# ESP8266-ESP201.net
KiCad netlist of a schematic drawn in EAGLE
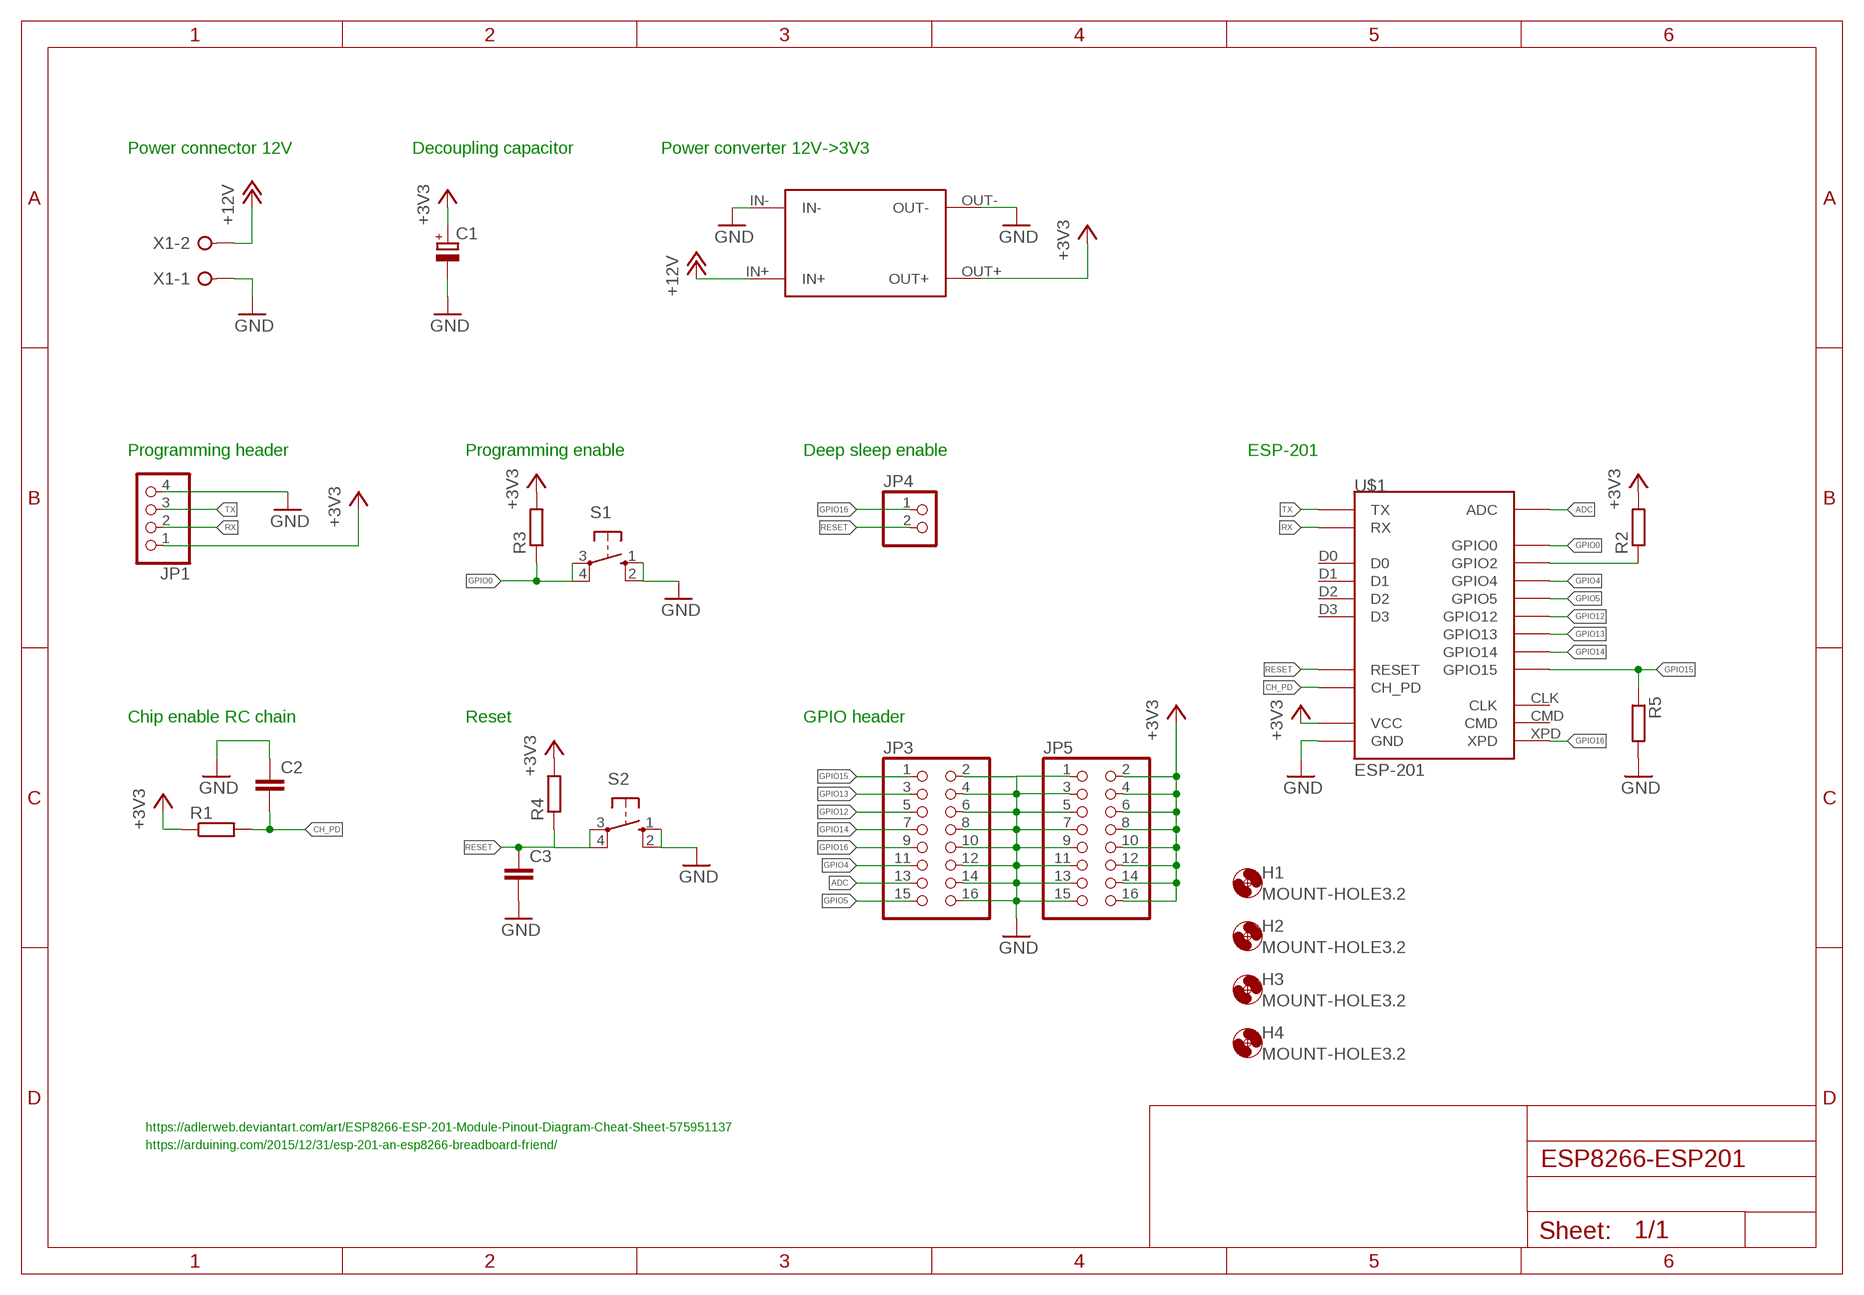
[diagram p0: schematic, sheet 1]

(export (version "E")
  (design (tool "Eeschema 10.0.6"))
  (components
    (comp (ref "C1")
      (value "CPOL-EUE2.5-5")
      (footprint "eagle-import:E2,5-5")
      (libsource (lib "eagle-import") (part "CPOL-EUE2.5-5"))
    )
    (comp (ref "C2")
      (value "C-EU025-024X044")
      (footprint "eagle-import:C025-024X044")
      (libsource (lib "eagle-import") (part "C-EU025-024X044"))
    )
    (comp (ref "C3")
      (value "C-EU025-024X044")
      (footprint "eagle-import:C025-024X044")
      (libsource (lib "eagle-import") (part "C-EU025-024X044"))
    )
    (comp (ref "H1")
      (value "MOUNT-HOLE3.2")
      (footprint "eagle-import:3,2")
      (libsource (lib "eagle-import") (part "MOUNT-HOLE3.2"))
    )
    (comp (ref "H2")
      (value "MOUNT-HOLE3.2")
      (footprint "eagle-import:3,2")
      (libsource (lib "eagle-import") (part "MOUNT-HOLE3.2"))
    )
    (comp (ref "H3")
      (value "MOUNT-HOLE3.2")
      (footprint "eagle-import:3,2")
      (libsource (lib "eagle-import") (part "MOUNT-HOLE3.2"))
    )
    (comp (ref "H4")
      (value "MOUNT-HOLE3.2")
      (footprint "eagle-import:3,2")
      (libsource (lib "eagle-import") (part "MOUNT-HOLE3.2"))
    )
    (comp (ref "JP1")
      (value "PINHD-1X4")
      (footprint "eagle-import:1X04")
      (libsource (lib "eagle-import") (part "PINHD-1X4"))
    )
    (comp (ref "JP3")
      (value "PINHD-2X8")
      (footprint "eagle-import:2X08")
      (libsource (lib "eagle-import") (part "PINHD-2X8"))
    )
    (comp (ref "JP4")
      (value "PINHD-1X2")
      (footprint "eagle-import:1X02")
      (libsource (lib "eagle-import") (part "PINHD-1X2"))
    )
    (comp (ref "JP5")
      (value "PINHD-2X8")
      (footprint "eagle-import:2X08")
      (libsource (lib "eagle-import") (part "PINHD-2X8"))
    )
    (comp (ref "R1")
      (value "R-EU_0207/10")
      (footprint "eagle-import:0207_10")
      (libsource (lib "eagle-import") (part "R-EU_0207/10"))
    )
    (comp (ref "R2")
      (value "R-EU_0207/10")
      (footprint "eagle-import:0207_10")
      (libsource (lib "eagle-import") (part "R-EU_0207/10"))
    )
    (comp (ref "R3")
      (value "R-EU_0207/10")
      (footprint "eagle-import:0207_10")
      (libsource (lib "eagle-import") (part "R-EU_0207/10"))
    )
    (comp (ref "R4")
      (value "R-EU_0207/10")
      (footprint "eagle-import:0207_10")
      (libsource (lib "eagle-import") (part "R-EU_0207/10"))
    )
    (comp (ref "R5")
      (value "R-EU_0207/10")
      (footprint "eagle-import:0207_10")
      (libsource (lib "eagle-import") (part "R-EU_0207/10"))
    )
    (comp (ref "S1")
      (value "10-XX")
      (footprint "eagle-import:B3F-10XX")
      (fields (field (name "MPN") "B3F-1000"))
      (libsource (lib "eagle-import") (part "10-XX"))
    )
    (comp (ref "S2")
      (value "10-XX")
      (footprint "eagle-import:B3F-10XX")
      (fields (field (name "MPN") "B3F-1000"))
      (libsource (lib "eagle-import") (part "10-XX"))
    )
    (comp (ref "U$1")
      (value "ESP-201")
      (footprint "eagle-import:ESP-201")
      (libsource (lib "eagle-import") (part "ESP-201"))
    )
    (comp (ref "U$2")
      (value "MINI360")
      (footprint "eagle-import:MINI360")
      (libsource (lib "eagle-import") (part "MINI360"))
    )
    (comp (ref "X1")
      (value "W237-02P")
      (footprint "eagle-import:W237-132")
      (libsource (lib "eagle-import") (part "W237-02P"))
    )
  )
  (nets
    (net (code "1") (name "+3V3") (class "Default")
      (node (ref "C1") (pin "+") (pinfunction "+_+") (pintype "passive"))
      (node (ref "JP1") (pin "1") (pinfunction "1_1") (pintype "passive"))
      (node (ref "JP5") (pin "10") (pinfunction "10_10") (pintype "passive"))
      (node (ref "JP5") (pin "12") (pinfunction "12_12") (pintype "passive"))
      (node (ref "JP5") (pin "14") (pinfunction "14_14") (pintype "passive"))
      (node (ref "JP5") (pin "16") (pinfunction "16_16") (pintype "passive"))
      (node (ref "JP5") (pin "2") (pinfunction "2_2") (pintype "passive"))
      (node (ref "JP5") (pin "4") (pinfunction "4_4") (pintype "passive"))
      (node (ref "JP5") (pin "6") (pinfunction "6_6") (pintype "passive"))
      (node (ref "JP5") (pin "8") (pinfunction "8_8") (pintype "passive"))
      (node (ref "R1") (pin "1") (pinfunction "1_1") (pintype "passive"))
      (node (ref "R2") (pin "2") (pinfunction "2_2") (pintype "passive"))
      (node (ref "R3") (pin "2") (pinfunction "2_2") (pintype "passive"))
      (node (ref "R4") (pin "2") (pinfunction "2_2") (pintype "passive"))
      (node (ref "U$1") (pin "3V3") (pinfunction "VCC_3V3") (pintype "bidirectional"))
      (node (ref "U$1") (pin "3V3_2") (pinfunction "VCC_3V3_2") (pintype "bidirectional"))
      (node (ref "U$1") (pin "3V3_3") (pinfunction "VCC_3V3_3") (pintype "bidirectional"))
      (node (ref "U$2") (pin "OUT+") (pinfunction "OUT+_OUT+") (pintype "bidirectional"))
    )
    (net (code "2") (name "+12V") (class "Default")
      (node (ref "U$2") (pin "IN+") (pinfunction "IN+_IN+") (pintype "bidirectional"))
      (node (ref "X1") (pin "2") (pinfunction "KL_2") (pintype "passive"))
    )
    (net (code "3") (name "ADC") (class "Default")
      (node (ref "JP3") (pin "13") (pinfunction "13_13") (pintype "passive"))
      (node (ref "U$1") (pin "ADC") (pinfunction "ADC_ADC") (pintype "bidirectional"))
    )
    (net (code "4") (name "CH_PD") (class "Default")
      (node (ref "C2") (pin "2") (pinfunction "2_2") (pintype "passive"))
      (node (ref "R1") (pin "2") (pinfunction "2_2") (pintype "passive"))
      (node (ref "U$1") (pin "CH_PD") (pinfunction "CH_PD_CH_PD") (pintype "bidirectional"))
    )
    (net (code "5") (name "GND") (class "Default")
      (node (ref "C1") (pin "-") (pinfunction "-_-") (pintype "passive"))
      (node (ref "C2") (pin "1") (pinfunction "1_1") (pintype "passive"))
      (node (ref "C3") (pin "2") (pinfunction "2_2") (pintype "passive"))
      (node (ref "JP1") (pin "4") (pinfunction "4_4") (pintype "passive"))
      (node (ref "JP3") (pin "10") (pinfunction "10_10") (pintype "passive"))
      (node (ref "JP3") (pin "12") (pinfunction "12_12") (pintype "passive"))
      (node (ref "JP3") (pin "14") (pinfunction "14_14") (pintype "passive"))
      (node (ref "JP3") (pin "16") (pinfunction "16_16") (pintype "passive"))
      (node (ref "JP3") (pin "2") (pinfunction "2_2") (pintype "passive"))
      (node (ref "JP3") (pin "4") (pinfunction "4_4") (pintype "passive"))
      (node (ref "JP3") (pin "6") (pinfunction "6_6") (pintype "passive"))
      (node (ref "JP3") (pin "8") (pinfunction "8_8") (pintype "passive"))
      (node (ref "JP5") (pin "1") (pinfunction "1_1") (pintype "passive"))
      (node (ref "JP5") (pin "11") (pinfunction "11_11") (pintype "passive"))
      (node (ref "JP5") (pin "13") (pinfunction "13_13") (pintype "passive"))
      (node (ref "JP5") (pin "15") (pinfunction "15_15") (pintype "passive"))
      (node (ref "JP5") (pin "3") (pinfunction "3_3") (pintype "passive"))
      (node (ref "JP5") (pin "5") (pinfunction "5_5") (pintype "passive"))
      (node (ref "JP5") (pin "7") (pinfunction "7_7") (pintype "passive"))
      (node (ref "JP5") (pin "9") (pinfunction "9_9") (pintype "passive"))
      (node (ref "R5") (pin "2") (pinfunction "2_2") (pintype "passive"))
      (node (ref "S1") (pin "1") (pinfunction "S_1") (pintype "passive"))
      (node (ref "S1") (pin "2") (pinfunction "S1_2") (pintype "passive"))
      (node (ref "S2") (pin "1") (pinfunction "S_1") (pintype "passive"))
      (node (ref "S2") (pin "2") (pinfunction "S1_2") (pintype "passive"))
      (node (ref "U$1") (pin "GND") (pinfunction "GND_GND") (pintype "bidirectional"))
      (node (ref "U$1") (pin "GND_2") (pinfunction "GND_GND_2") (pintype "bidirectional"))
      (node (ref "U$1") (pin "GND_3") (pinfunction "GND_GND_3") (pintype "bidirectional"))
      (node (ref "U$2") (pin "IN-") (pinfunction "IN-_IN-") (pintype "bidirectional"))
      (node (ref "U$2") (pin "OUT-") (pinfunction "OUT-_OUT-") (pintype "bidirectional"))
      (node (ref "X1") (pin "1") (pinfunction "KL_1") (pintype "passive"))
    )
    (net (code "6") (name "GPIO0") (class "Default")
      (node (ref "R3") (pin "1") (pinfunction "1_1") (pintype "passive"))
      (node (ref "S1") (pin "3") (pinfunction "P_3") (pintype "passive"))
      (node (ref "S1") (pin "4") (pinfunction "P1_4") (pintype "passive"))
      (node (ref "U$1") (pin "GPIO0") (pinfunction "GPIO0_GPIO0") (pintype "bidirectional"))
    )
    (net (code "7") (name "GPIO4") (class "Default")
      (node (ref "JP3") (pin "11") (pinfunction "11_11") (pintype "passive"))
      (node (ref "U$1") (pin "GPIO4") (pinfunction "GPIO4_GPIO4") (pintype "bidirectional"))
    )
    (net (code "8") (name "GPIO5") (class "Default")
      (node (ref "JP3") (pin "15") (pinfunction "15_15") (pintype "passive"))
      (node (ref "U$1") (pin "GPIO5") (pinfunction "GPIO5_GPIO5") (pintype "bidirectional"))
    )
    (net (code "9") (name "GPIO12") (class "Default")
      (node (ref "JP3") (pin "5") (pinfunction "5_5") (pintype "passive"))
      (node (ref "U$1") (pin "GPIO12") (pinfunction "GPIO12_GPIO12") (pintype "bidirectional"))
    )
    (net (code "10") (name "GPIO13") (class "Default")
      (node (ref "JP3") (pin "3") (pinfunction "3_3") (pintype "passive"))
      (node (ref "U$1") (pin "GPIO13") (pinfunction "GPIO13_GPIO13") (pintype "bidirectional"))
    )
    (net (code "11") (name "GPIO14") (class "Default")
      (node (ref "JP3") (pin "7") (pinfunction "7_7") (pintype "passive"))
      (node (ref "U$1") (pin "GPIO14") (pinfunction "GPIO14_GPIO14") (pintype "bidirectional"))
    )
    (net (code "12") (name "GPIO15") (class "Default")
      (node (ref "JP3") (pin "1") (pinfunction "1_1") (pintype "passive"))
      (node (ref "R5") (pin "1") (pinfunction "1_1") (pintype "passive"))
      (node (ref "U$1") (pin "GPIO15") (pinfunction "GPIO15_GPIO15") (pintype "bidirectional"))
    )
    (net (code "13") (name "GPIO16") (class "Default")
      (node (ref "JP3") (pin "9") (pinfunction "9_9") (pintype "passive"))
      (node (ref "JP4") (pin "1") (pinfunction "1_1") (pintype "passive"))
      (node (ref "U$1") (pin "XPD") (pinfunction "XPD_XPD") (pintype "bidirectional"))
    )
    (net (code "14") (name "Net-(R2-Pad1)") (class "Default")
      (node (ref "R2") (pin "1") (pinfunction "1_1") (pintype "passive"))
      (node (ref "U$1") (pin "GPIO2") (pinfunction "GPIO2_GPIO2") (pintype "bidirectional"))
    )
    (net (code "15") (name "RESET") (class "Default")
      (node (ref "C3") (pin "1") (pinfunction "1_1") (pintype "passive"))
      (node (ref "JP4") (pin "2") (pinfunction "2_2") (pintype "passive"))
      (node (ref "R4") (pin "1") (pinfunction "1_1") (pintype "passive"))
      (node (ref "S2") (pin "3") (pinfunction "P_3") (pintype "passive"))
      (node (ref "S2") (pin "4") (pinfunction "P1_4") (pintype "passive"))
      (node (ref "U$1") (pin "RST") (pinfunction "RESET_RST") (pintype "bidirectional"))
    )
    (net (code "16") (name "RX") (class "Default")
      (node (ref "JP1") (pin "2") (pinfunction "2_2") (pintype "passive"))
      (node (ref "U$1") (pin "RX") (pinfunction "RX_RX") (pintype "bidirectional"))
    )
    (net (code "17") (name "TX") (class "Default")
      (node (ref "JP1") (pin "3") (pinfunction "3_3") (pintype "passive"))
      (node (ref "U$1") (pin "TX") (pinfunction "TX_TX") (pintype "bidirectional"))
    )
    (net (code "18") (name "unconnected-(U$1-PadCLK)") (class "Default")
      (node (ref "U$1") (pin "CLK") (pinfunction "CLK_CLK") (pintype "bidirectional"))
    )
    (net (code "19") (name "unconnected-(U$1-PadCMD)") (class "Default")
      (node (ref "U$1") (pin "CMD") (pinfunction "CMD_CMD") (pintype "bidirectional"))
    )
    (net (code "20") (name "unconnected-(U$1-PadD0)") (class "Default")
      (node (ref "U$1") (pin "D0") (pinfunction "D0_D0") (pintype "bidirectional"))
    )
    (net (code "21") (name "unconnected-(U$1-PadD1)") (class "Default")
      (node (ref "U$1") (pin "D1") (pinfunction "D1_D1") (pintype "bidirectional"))
    )
    (net (code "22") (name "unconnected-(U$1-PadD2)") (class "Default")
      (node (ref "U$1") (pin "D2") (pinfunction "D2_D2") (pintype "bidirectional"))
    )
    (net (code "23") (name "unconnected-(U$1-PadD3)") (class "Default")
      (node (ref "U$1") (pin "D3") (pinfunction "D3_D3") (pintype "bidirectional"))
    )
  )
)
